# SCH_Elektrisch_Schema_B_2022-10-22.net
KiCad netlist of a schematic drawn in EasyEDA
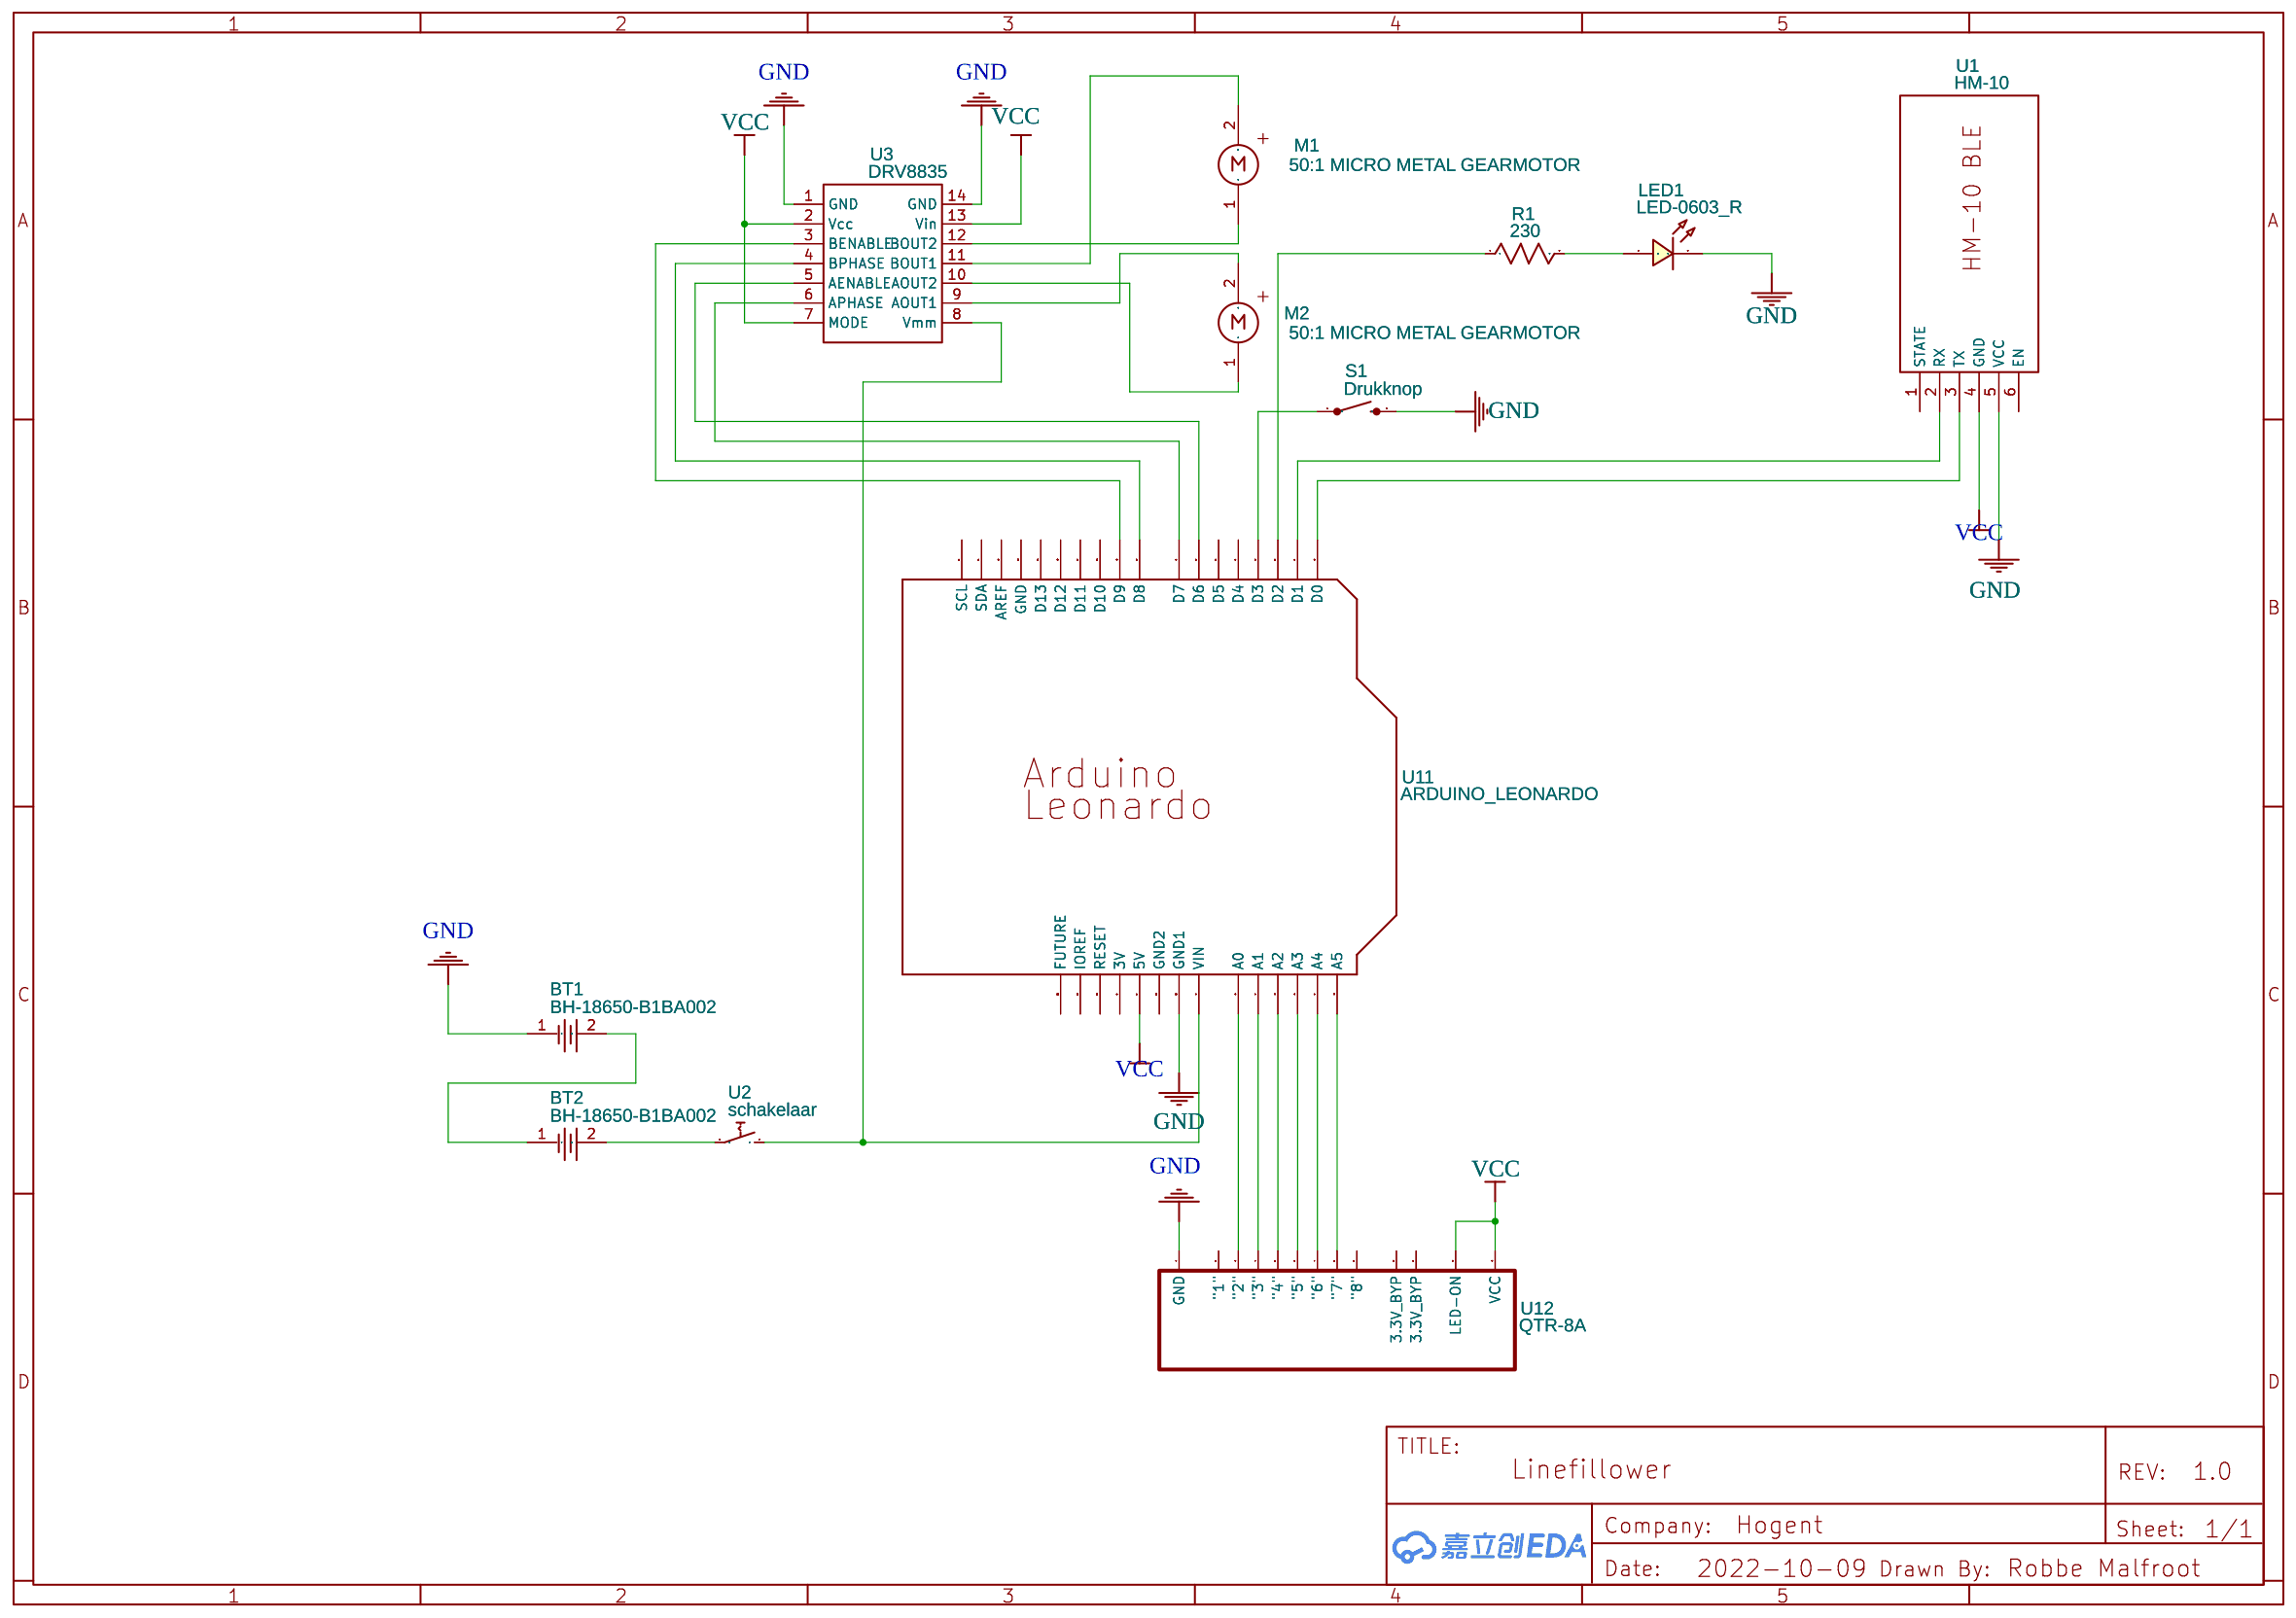
[diagram p0: Elektrisch schema B]
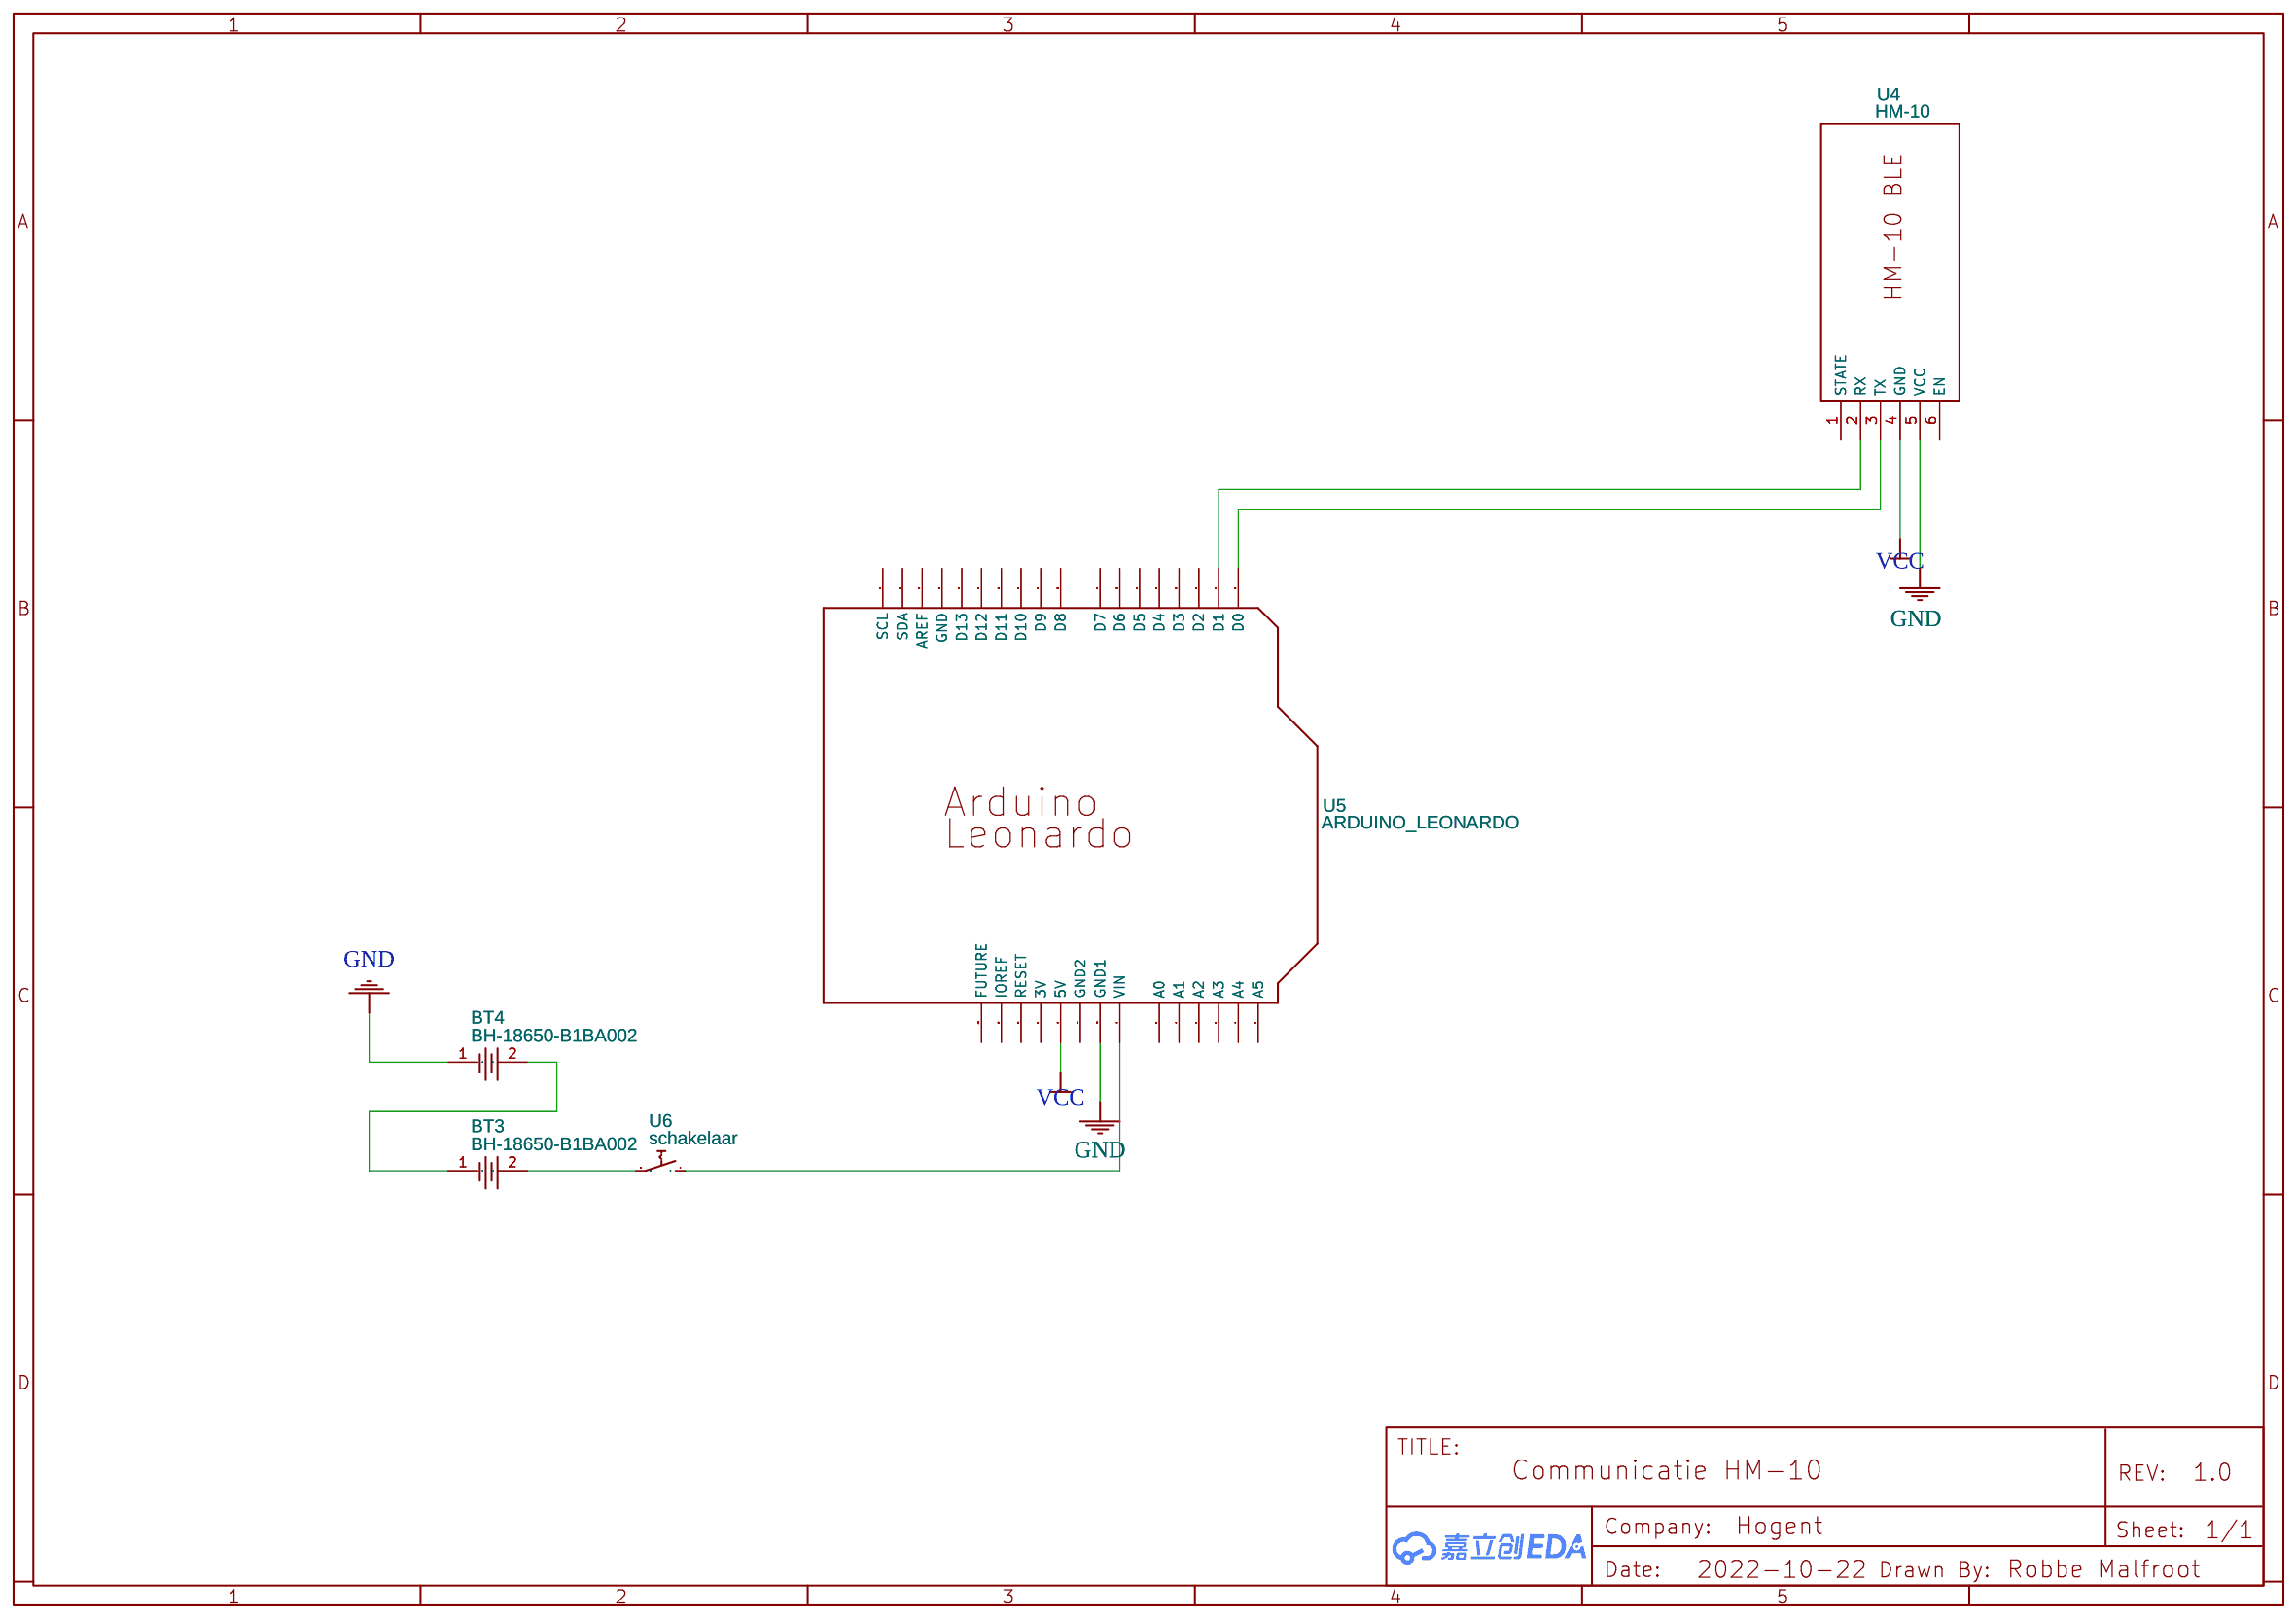
[diagram p1: Communicatie_HM-10]
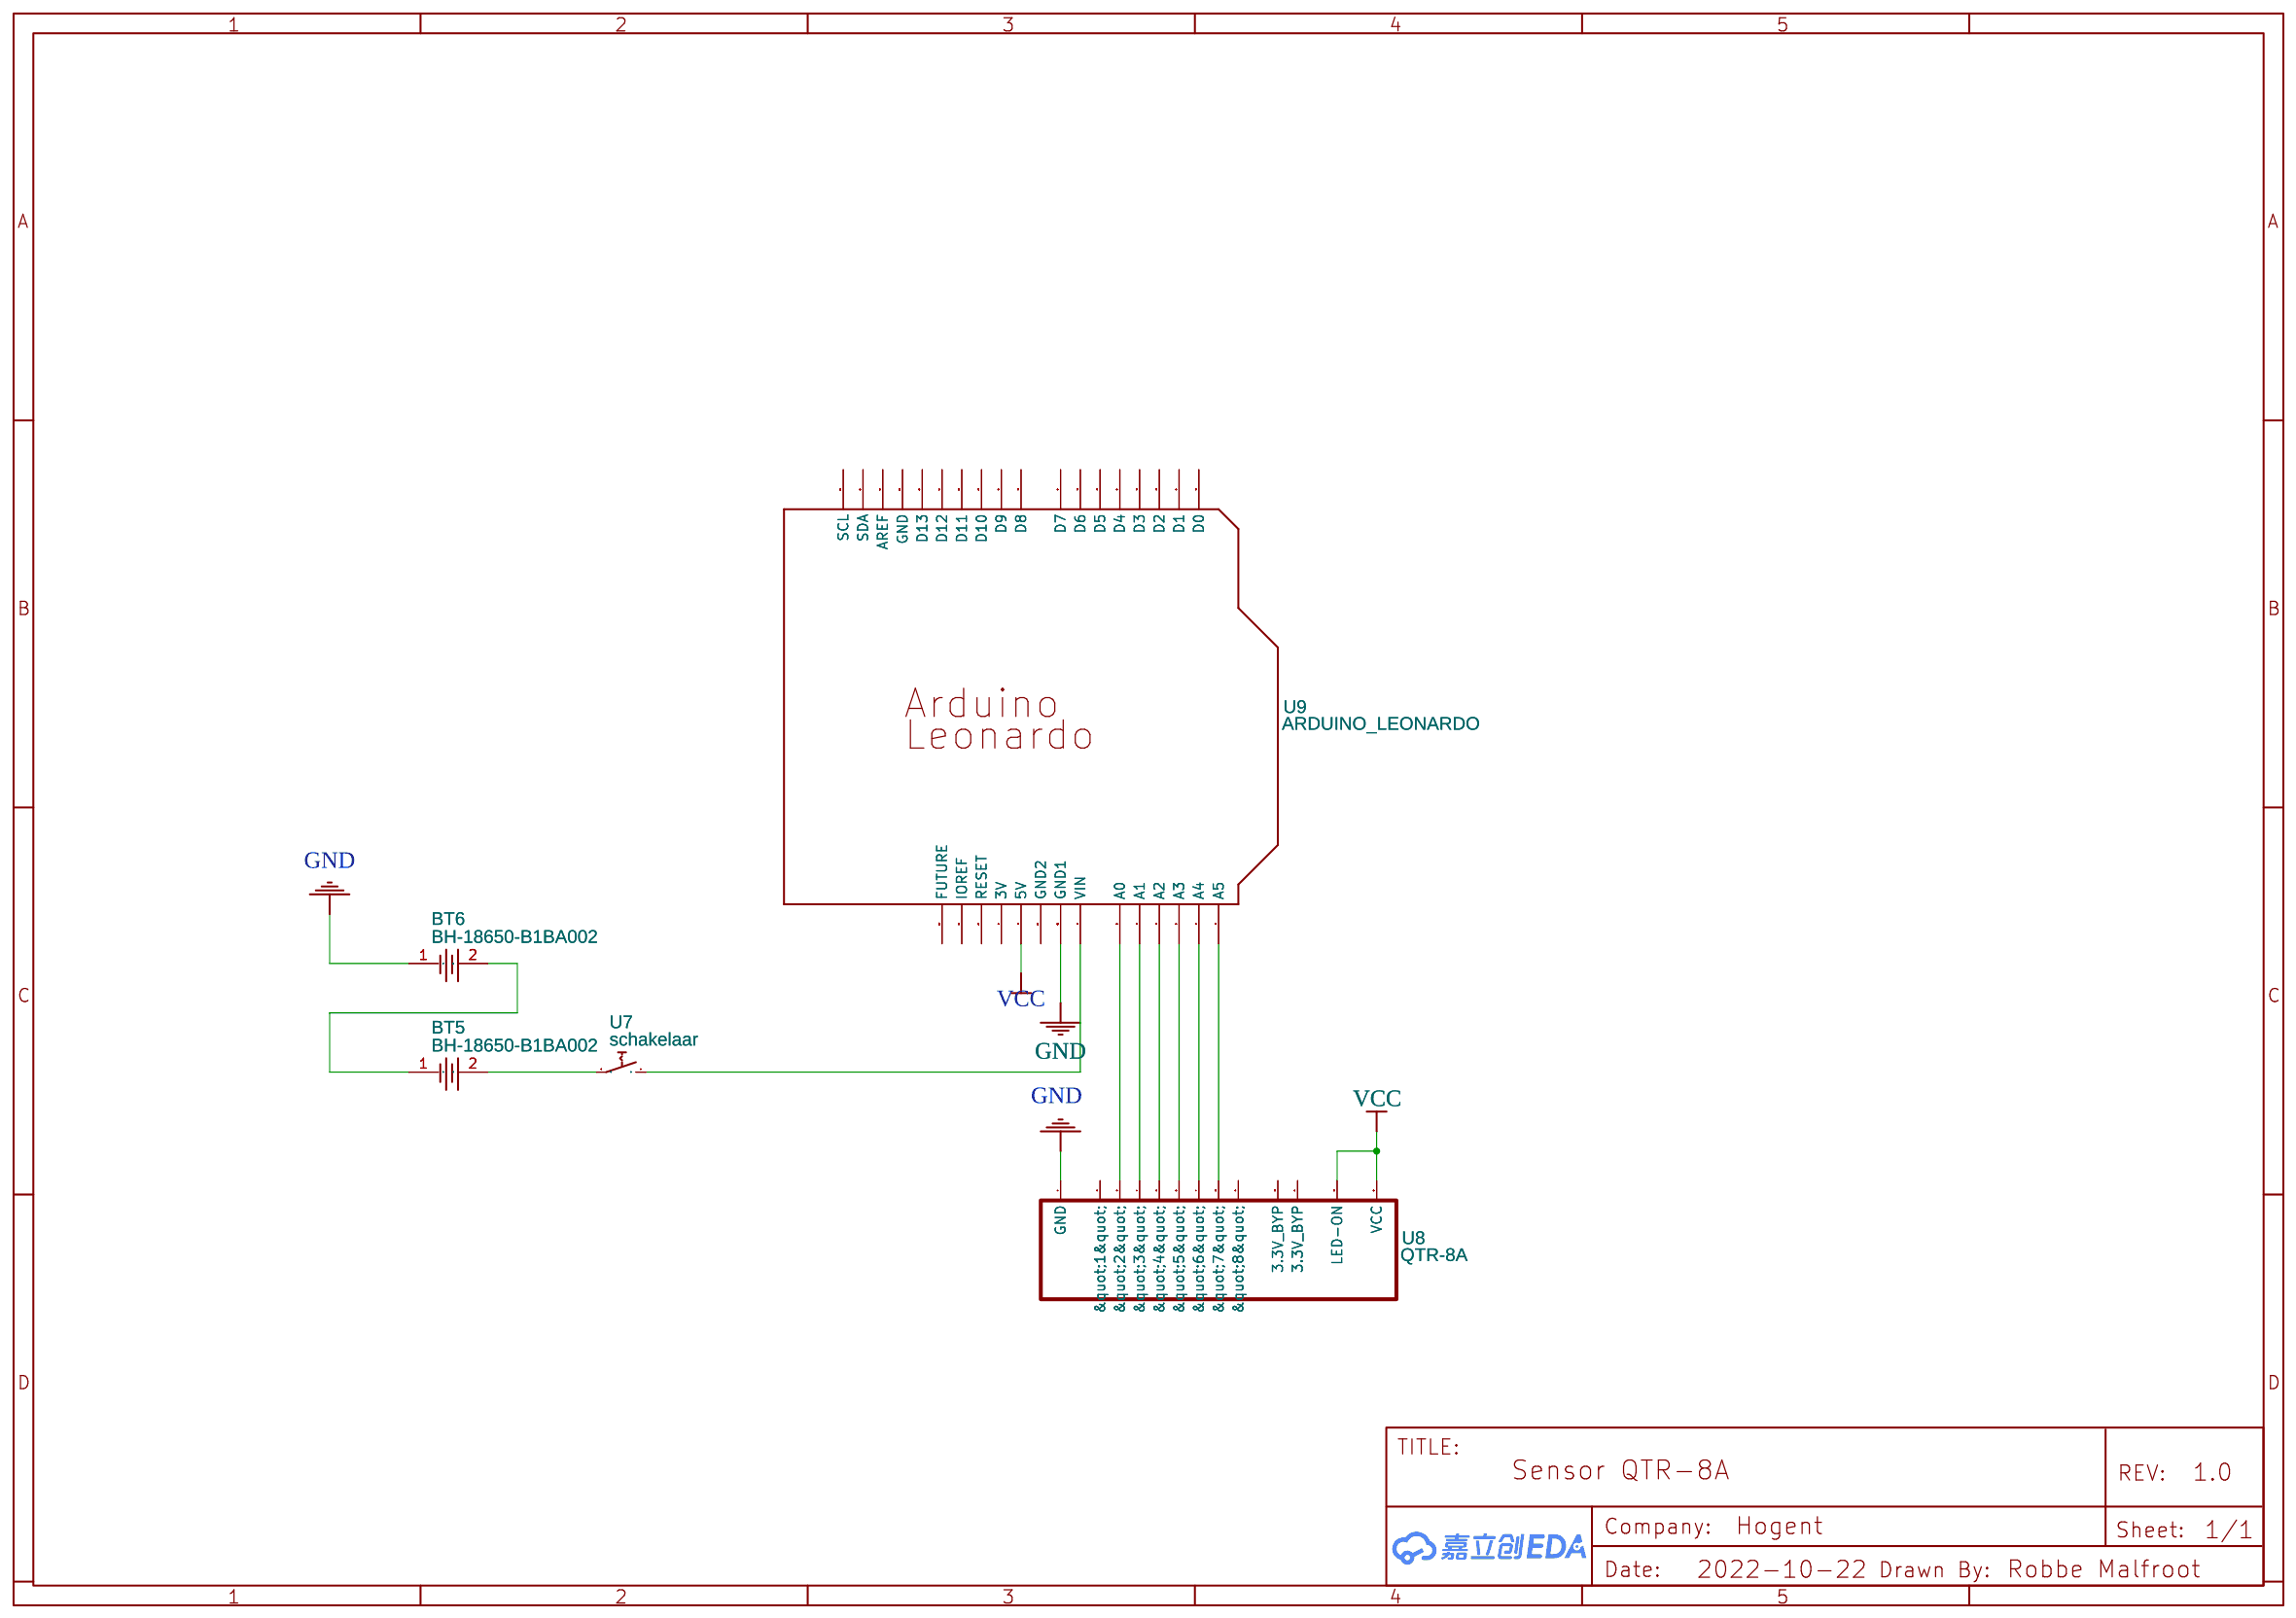
[diagram p2: QTR-8A]
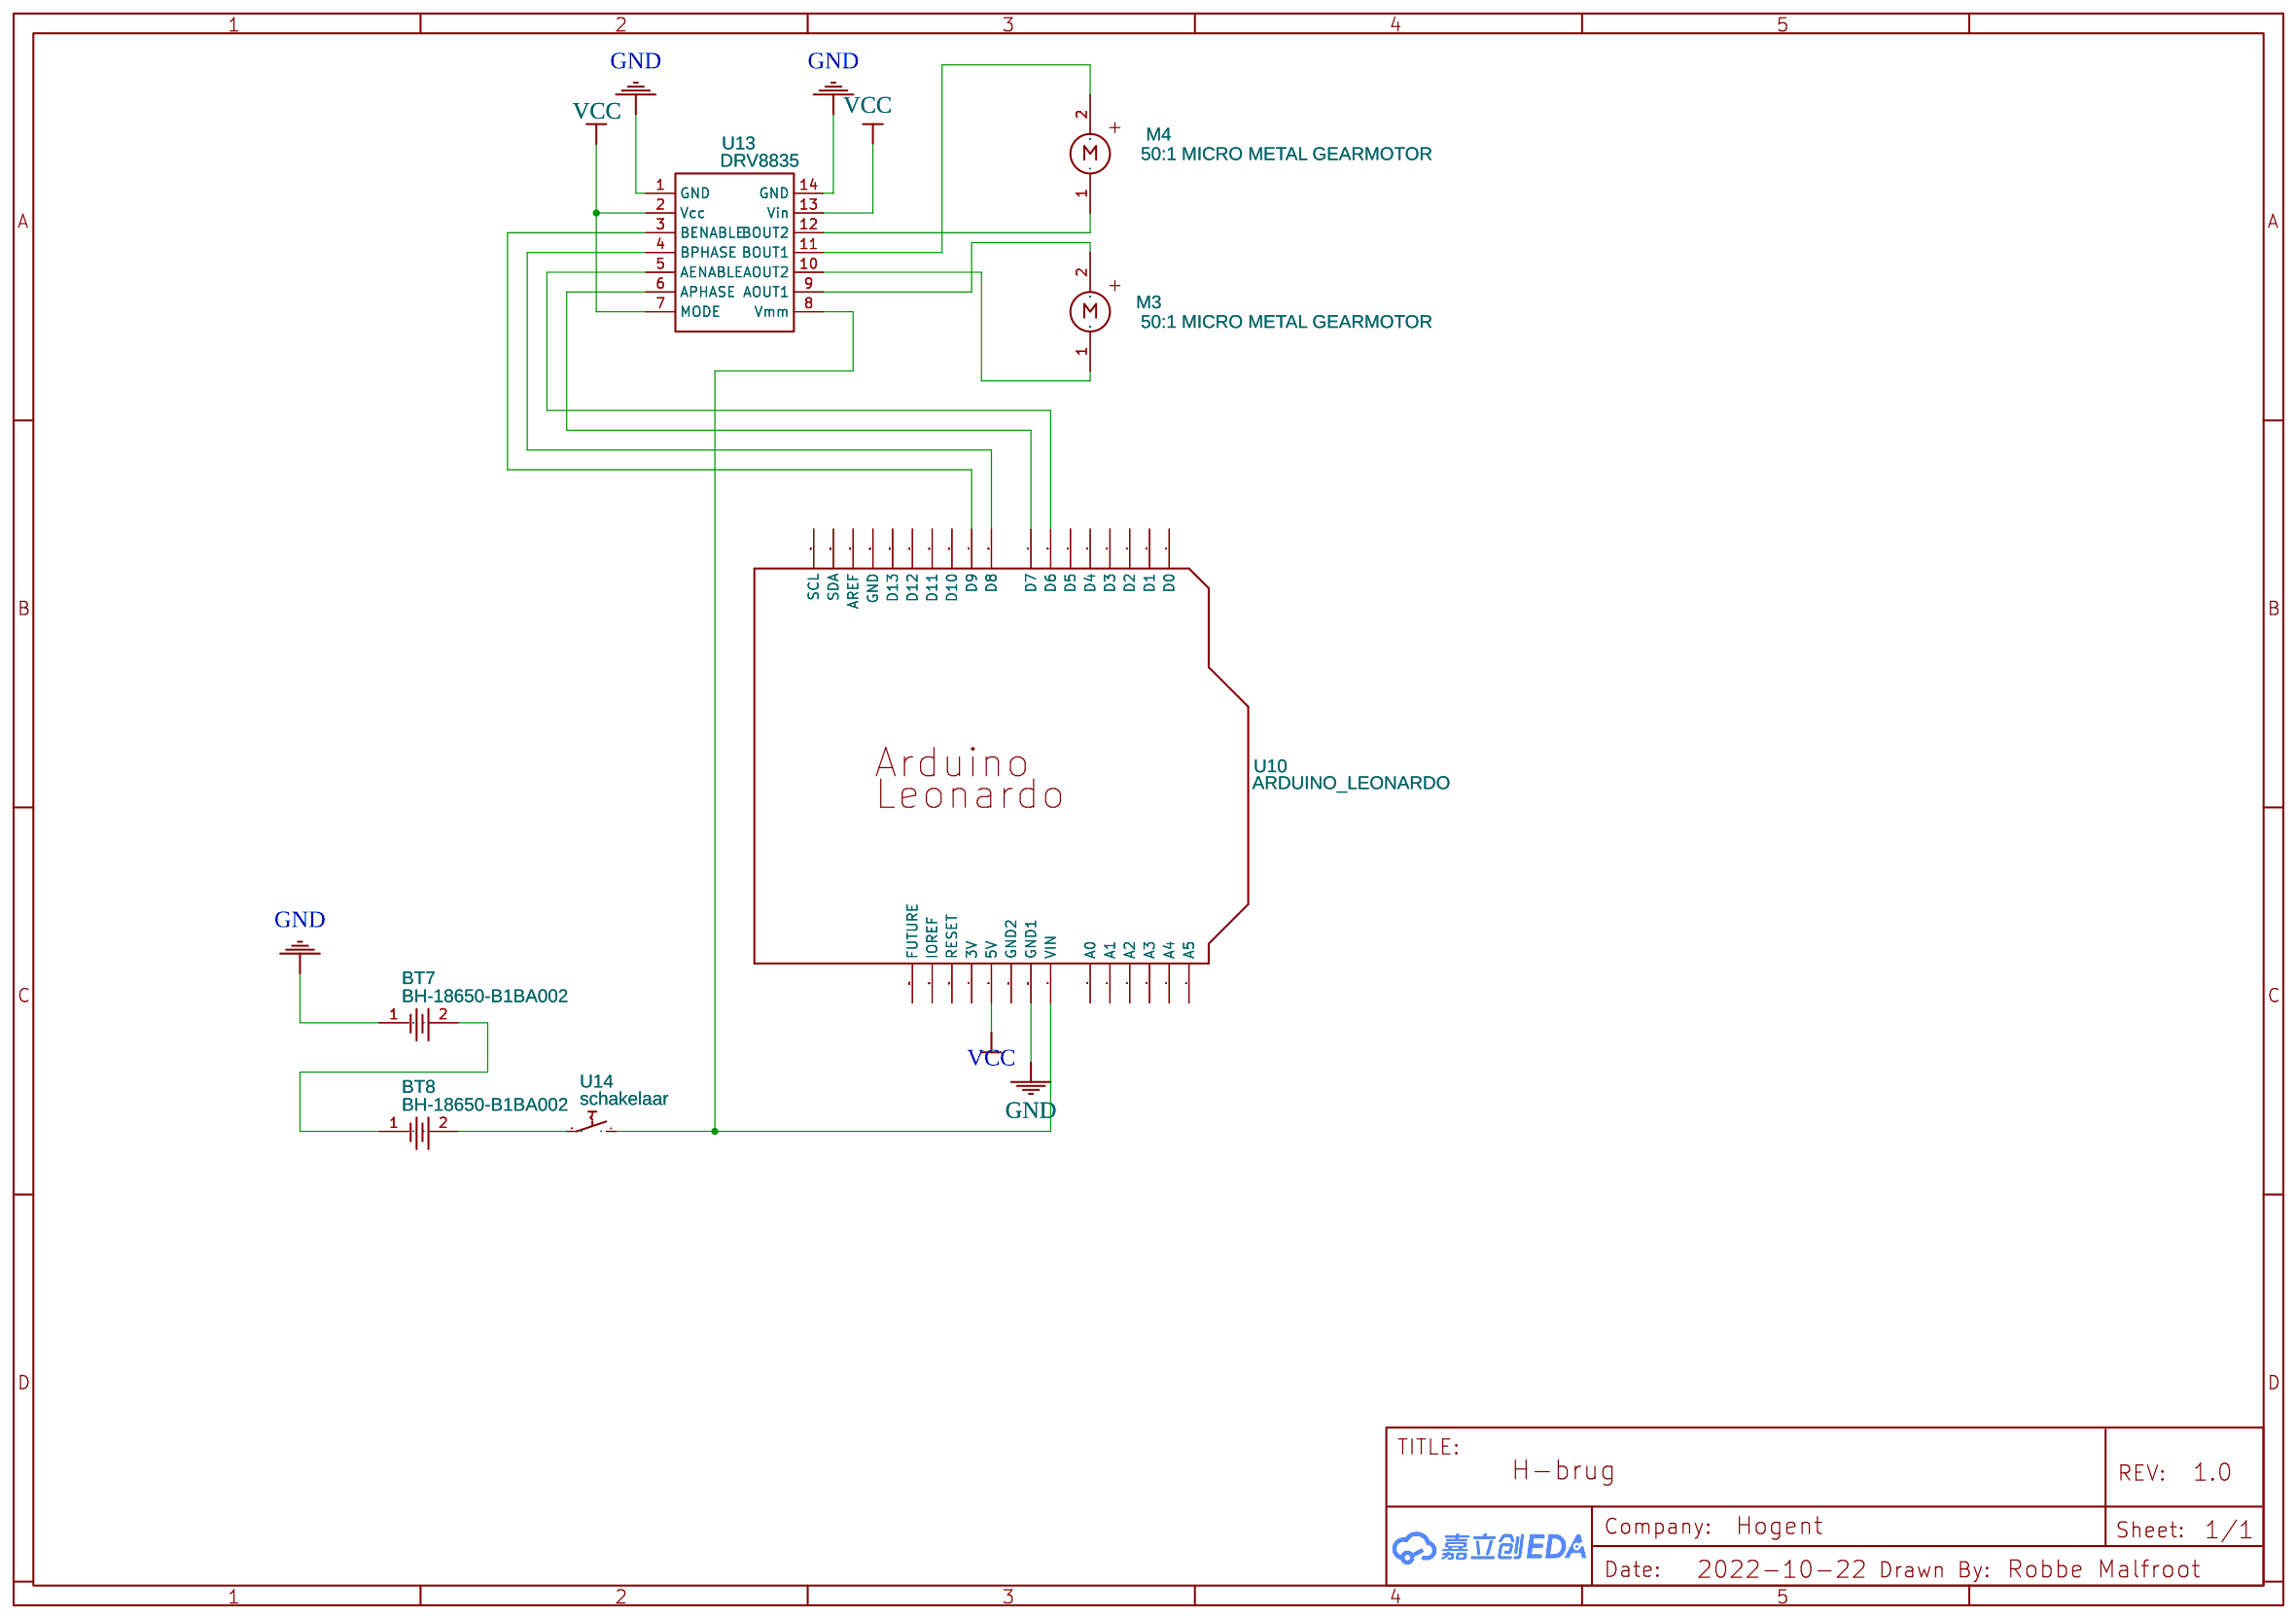
[diagram p3: H-brug DRV8835]

(export (version "E")
  (design (tool "Eeschema 10.0.6"))
  (components
    (comp (ref "BT1")
      (value "BH-18650-B1BA002")
      (fields (field (name "BOM_Supplier Part") "C2988620"))
      (libsource (lib "") (part "BH-18650-B1BA002"))
    )
    (comp (ref "BT2")
      (value "BH-18650-B1BA002")
      (fields (field (name "BOM_Supplier Part") "C2988620"))
      (libsource (lib "") (part "BH-18650-B1BA002"))
    )
    (comp (ref "LED1")
      (value "LED-0603_R")
      (fields
        (field (name "BOM_Manufacturer Part") "19-217/R6C-AL1M2VY/3T")
        (field (name "BOM_Supplier Part") "C72044")
      )
      (libsource (lib "") (part "LED-0603_R"))
    )
    (comp (ref "M1")
      (value "50:1 MICRO METAL GEARMOTOR")
      (fields
        (field (name "BOM_Manufacturer Part") "10:1 Micro Metal Gearmotor HPCB 6V with Extended Motor Shaft")
        (field (name "BOM_Supplier Part") "3071")
      )
      (libsource (lib "") (part "10{colon}1 MICRO METAL GEARMOTOR eskere"))
    )
    (comp (ref "M2")
      (value "50:1 MICRO METAL GEARMOTOR")
      (fields
        (field (name "BOM_Manufacturer Part") "10:1 Micro Metal Gearmotor HPCB 6V with Extended Motor Shaft")
        (field (name "BOM_Supplier Part") "3071")
      )
      (libsource (lib "") (part "10{colon}1 MICRO METAL GEARMOTOR eskere"))
    )
    (comp (ref "R1") (value "230") (libsource (lib "") (part "R_0603_US")))
    (comp (ref "S1") (value "Drukknop") (libsource (lib "") (part "Drukknop")))
    (comp (ref "U1") (value "HM-10") (libsource (lib "") (part "HM-10")))
    (comp (ref "U2") (value "schakelaar") (libsource (lib "") (part "schakelaar")))
    (comp (ref "U3") (value "DRV8835") (libsource (lib "") (part "DRV8835")))
    (comp (ref "U11") (value "ARDUINO_LEONARDO") (libsource (lib "") (part "ARDUINO_LEONARDO")))
    (comp (ref "U12")
      (value "QTR-8A")
      (fields (field (name "BOM_Supplier Part") "960"))
      (libsource (lib "") (part "QTR-8A"))
    )
    (comp (ref "BT3")
      (value "BH-18650-B1BA002")
      (fields (field (name "BOM_Supplier Part") "C2988620"))
      (libsource (lib "") (part "BH-18650-B1BA002"))
    )
    (comp (ref "BT4")
      (value "BH-18650-B1BA002")
      (fields (field (name "BOM_Supplier Part") "C2988620"))
      (libsource (lib "") (part "BH-18650-B1BA002"))
    )
    (comp (ref "U4") (value "HM-10") (libsource (lib "") (part "HM-10")))
    (comp (ref "U5") (value "ARDUINO_LEONARDO") (libsource (lib "") (part "ARDUINO_LEONARDO")))
    (comp (ref "U6") (value "schakelaar") (libsource (lib "") (part "schakelaar")))
    (comp (ref "BT5")
      (value "BH-18650-B1BA002")
      (fields (field (name "BOM_Supplier Part") "C2988620"))
      (libsource (lib "") (part "BH-18650-B1BA002"))
    )
    (comp (ref "BT6")
      (value "BH-18650-B1BA002")
      (fields (field (name "BOM_Supplier Part") "C2988620"))
      (libsource (lib "") (part "BH-18650-B1BA002"))
    )
    (comp (ref "U7") (value "schakelaar") (libsource (lib "") (part "schakelaar")))
    (comp (ref "U8")
      (value "QTR-8A")
      (fields (field (name "BOM_Supplier Part") "960"))
      (libsource (lib "") (part "QTR-8A"))
    )
    (comp (ref "U9") (value "ARDUINO_LEONARDO") (libsource (lib "") (part "ARDUINO_LEONARDO")))
    (comp (ref "BT7")
      (value "BH-18650-B1BA002")
      (fields (field (name "BOM_Supplier Part") "C2988620"))
      (libsource (lib "") (part "BH-18650-B1BA002"))
    )
    (comp (ref "BT8")
      (value "BH-18650-B1BA002")
      (fields (field (name "BOM_Supplier Part") "C2988620"))
      (libsource (lib "") (part "BH-18650-B1BA002"))
    )
    (comp (ref "M3")
      (value "50:1 MICRO METAL GEARMOTOR")
      (fields
        (field (name "BOM_Manufacturer Part") "10:1 Micro Metal Gearmotor HPCB 6V with Extended Motor Shaft")
        (field (name "BOM_Supplier Part") "3071")
      )
      (libsource (lib "") (part "10{colon}1 MICRO METAL GEARMOTOR eskere"))
    )
    (comp (ref "M4")
      (value "50:1 MICRO METAL GEARMOTOR")
      (fields
        (field (name "BOM_Manufacturer Part") "10:1 Micro Metal Gearmotor HPCB 6V with Extended Motor Shaft")
        (field (name "BOM_Supplier Part") "3071")
      )
      (libsource (lib "") (part "10{colon}1 MICRO METAL GEARMOTOR eskere"))
    )
    (comp (ref "U10") (value "ARDUINO_LEONARDO") (libsource (lib "") (part "ARDUINO_LEONARDO")))
    (comp (ref "U13") (value "DRV8835") (libsource (lib "") (part "DRV8835")))
    (comp (ref "U14") (value "schakelaar") (libsource (lib "") (part "schakelaar")))
  )
  (nets
    (net (code "1") (name "GND") (class "Default")
      (node (ref "BT1") (pin "1") (pinfunction "1_1") (pintype "input"))
      (node (ref "BT4") (pin "1") (pinfunction "1_1") (pintype "input"))
      (node (ref "BT6") (pin "1") (pinfunction "1_1") (pintype "input"))
      (node (ref "BT7") (pin "1") (pinfunction "1_1") (pintype "input"))
      (node (ref "LED1") (pin "2") (pinfunction "2_2") (pintype "unspecified"))
      (node (ref "S1") (pin "2") (pinfunction "2_2") (pintype "unspecified"))
      (node (ref "U1") (pin "5") (pinfunction "VCC_5") (pintype "unspecified"))
      (node (ref "U10") (pin "GND$3") (pinfunction "GND1_GND$3") (pintype "passive"))
      (node (ref "U11") (pin "GND$3") (pinfunction "GND1_GND$3") (pintype "passive"))
      (node (ref "U12") (pin "1") (pinfunction "GND_1") (pintype "unspecified"))
      (node (ref "U13") (pin "1") (pinfunction "GND_1") (pintype "unspecified"))
      (node (ref "U13") (pin "14") (pinfunction "GND_14") (pintype "unspecified"))
      (node (ref "U3") (pin "1") (pinfunction "GND_1") (pintype "unspecified"))
      (node (ref "U3") (pin "14") (pinfunction "GND_14") (pintype "unspecified"))
      (node (ref "U4") (pin "5") (pinfunction "VCC_5") (pintype "unspecified"))
      (node (ref "U5") (pin "GND$3") (pinfunction "GND1_GND$3") (pintype "passive"))
      (node (ref "U8") (pin "1") (pinfunction "GND_1") (pintype "unspecified"))
      (node (ref "U9") (pin "GND$3") (pinfunction "GND1_GND$3") (pintype "passive"))
    )
    (net (code "2") (name "Net-(BT1-Pad2)") (class "Default")
      (node (ref "BT1") (pin "2") (pinfunction "2_2") (pintype "input"))
      (node (ref "BT2") (pin "1") (pinfunction "1_1") (pintype "input"))
    )
    (net (code "3") (name "Net-(BT2-Pad2)") (class "Default")
      (node (ref "BT2") (pin "2") (pinfunction "2_2") (pintype "input"))
      (node (ref "U2") (pin "2") (pinfunction "2_2") (pintype "unspecified"))
    )
    (net (code "4") (name "Net-(BT3-Pad1)") (class "Default")
      (node (ref "BT3") (pin "1") (pinfunction "1_1") (pintype "input"))
      (node (ref "BT4") (pin "2") (pinfunction "2_2") (pintype "input"))
    )
    (net (code "5") (name "Net-(BT3-Pad2)") (class "Default")
      (node (ref "BT3") (pin "2") (pinfunction "2_2") (pintype "input"))
      (node (ref "U6") (pin "2") (pinfunction "2_2") (pintype "unspecified"))
    )
    (net (code "6") (name "Net-(BT5-Pad1)") (class "Default")
      (node (ref "BT5") (pin "1") (pinfunction "1_1") (pintype "input"))
      (node (ref "BT6") (pin "2") (pinfunction "2_2") (pintype "input"))
    )
    (net (code "7") (name "Net-(BT5-Pad2)") (class "Default")
      (node (ref "BT5") (pin "2") (pinfunction "2_2") (pintype "input"))
      (node (ref "U7") (pin "2") (pinfunction "2_2") (pintype "unspecified"))
    )
    (net (code "8") (name "Net-(BT7-Pad2)") (class "Default")
      (node (ref "BT7") (pin "2") (pinfunction "2_2") (pintype "input"))
      (node (ref "BT8") (pin "1") (pinfunction "1_1") (pintype "input"))
    )
    (net (code "9") (name "Net-(BT8-Pad2)") (class "Default")
      (node (ref "BT8") (pin "2") (pinfunction "2_2") (pintype "input"))
      (node (ref "U14") (pin "2") (pinfunction "2_2") (pintype "unspecified"))
    )
    (net (code "10") (name "Net-(LED1-Pad1)") (class "Default")
      (node (ref "LED1") (pin "1") (pinfunction "1_1") (pintype "unspecified"))
      (node (ref "R1") (pin "2") (pinfunction "2_2") (pintype "unspecified"))
    )
    (net (code "11") (name "Net-(R1-Pad1)") (class "Default")
      (node (ref "R1") (pin "1") (pinfunction "1_1") (pintype "unspecified"))
      (node (ref "U11") (pin "D2") (pinfunction "D2_D2") (pintype "unspecified"))
    )
    (net (code "12") (name "Net-(S1-Pad1)") (class "Default")
      (node (ref "S1") (pin "1") (pinfunction "1_1") (pintype "unspecified"))
      (node (ref "U11") (pin "D3") (pinfunction "D3_D3") (pintype "unspecified"))
    )
    (net (code "13") (name "Net-(U1-RX)") (class "Default")
      (node (ref "U1") (pin "2") (pinfunction "RX_2") (pintype "unspecified"))
      (node (ref "U11") (pin "D1") (pinfunction "D1_D1") (pintype "unspecified"))
    )
    (net (code "14") (name "Net-(U1-TX)") (class "Default")
      (node (ref "U1") (pin "3") (pinfunction "TX_3") (pintype "unspecified"))
      (node (ref "U11") (pin "D0") (pinfunction "D0_D0") (pintype "unspecified"))
    )
    (net (code "15") (name "Net-(U3-AENABLE)") (class "Default")
      (node (ref "U11") (pin "D6") (pinfunction "D6_D6") (pintype "unspecified"))
      (node (ref "U3") (pin "5") (pinfunction "AENABLE_5") (pintype "unspecified"))
    )
    (net (code "16") (name "Net-(U3-AOUT1)") (class "Default")
      (node (ref "M2") (pin "2") (pinfunction "2_2") (pintype "unspecified"))
      (node (ref "U3") (pin "9") (pinfunction "AOUT1_9") (pintype "unspecified"))
    )
    (net (code "17") (name "Net-(U3-AOUT2)") (class "Default")
      (node (ref "M2") (pin "1") (pinfunction "1_1") (pintype "unspecified"))
      (node (ref "U3") (pin "10") (pinfunction "AOUT2_10") (pintype "unspecified"))
    )
    (net (code "18") (name "Net-(U3-APHASE)") (class "Default")
      (node (ref "U11") (pin "D7") (pinfunction "D7_D7") (pintype "unspecified"))
      (node (ref "U3") (pin "6") (pinfunction "APHASE_6") (pintype "unspecified"))
    )
    (net (code "19") (name "Net-(U3-BENABLE)") (class "Default")
      (node (ref "U11") (pin "D9") (pinfunction "D9_D9") (pintype "unspecified"))
      (node (ref "U3") (pin "3") (pinfunction "BENABLE_3") (pintype "unspecified"))
    )
    (net (code "20") (name "Net-(U3-BOUT1)") (class "Default")
      (node (ref "M1") (pin "2") (pinfunction "2_2") (pintype "unspecified"))
      (node (ref "U3") (pin "11") (pinfunction "BOUT1_11") (pintype "unspecified"))
    )
    (net (code "21") (name "Net-(U3-BOUT2)") (class "Default")
      (node (ref "M1") (pin "1") (pinfunction "1_1") (pintype "unspecified"))
      (node (ref "U3") (pin "12") (pinfunction "BOUT2_12") (pintype "unspecified"))
    )
    (net (code "22") (name "Net-(U3-BPHASE)") (class "Default")
      (node (ref "U11") (pin "D8") (pinfunction "D8_D8") (pintype "unspecified"))
      (node (ref "U3") (pin "4") (pinfunction "BPHASE_4") (pintype "unspecified"))
    )
    (net (code "23") (name "Net-(U3-Vmm)") (class "Default")
      (node (ref "U11") (pin "VIN") (pinfunction "VIN_VIN") (pintype "passive"))
      (node (ref "U2") (pin "1") (pinfunction "1_1") (pintype "unspecified"))
      (node (ref "U3") (pin "8") (pinfunction "Vmm_8") (pintype "unspecified"))
    )
    (net (code "24") (name "Net-(U4-RX)") (class "Default")
      (node (ref "U4") (pin "2") (pinfunction "RX_2") (pintype "unspecified"))
      (node (ref "U5") (pin "D1") (pinfunction "D1_D1") (pintype "unspecified"))
    )
    (net (code "25") (name "Net-(U4-TX)") (class "Default")
      (node (ref "U4") (pin "3") (pinfunction "TX_3") (pintype "unspecified"))
      (node (ref "U5") (pin "D0") (pinfunction "D0_D0") (pintype "unspecified"))
    )
    (net (code "26") (name "Net-(U5-PadVIN)") (class "Default")
      (node (ref "U5") (pin "VIN") (pinfunction "VIN_VIN") (pintype "passive"))
      (node (ref "U6") (pin "1") (pinfunction "1_1") (pintype "unspecified"))
    )
    (net (code "27") (name "Net-(U7-Pad1)") (class "Default")
      (node (ref "U7") (pin "1") (pinfunction "1_1") (pintype "unspecified"))
      (node (ref "U9") (pin "VIN") (pinfunction "VIN_VIN") (pintype "passive"))
    )
    (net (code "28") (name "Net-(U8-&quot;2&quot;)") (class "Default")
      (node (ref "U8") (pin "3") (pinfunction "&quot;2&quot;_3") (pintype "unspecified"))
      (node (ref "U9") (pin "A0") (pinfunction "A0_A0") (pintype "unspecified"))
    )
    (net (code "29") (name "Net-(U8-&quot;3&quot;)") (class "Default")
      (node (ref "U8") (pin "4") (pinfunction "&quot;3&quot;_4") (pintype "unspecified"))
      (node (ref "U9") (pin "A1") (pinfunction "A1_A1") (pintype "unspecified"))
    )
    (net (code "30") (name "Net-(U8-&quot;4&quot;)") (class "Default")
      (node (ref "U8") (pin "5") (pinfunction "&quot;4&quot;_5") (pintype "unspecified"))
      (node (ref "U9") (pin "A2") (pinfunction "A2_A2") (pintype "unspecified"))
    )
    (net (code "31") (name "Net-(U8-&quot;5&quot;)") (class "Default")
      (node (ref "U8") (pin "6") (pinfunction "&quot;5&quot;_6") (pintype "unspecified"))
      (node (ref "U9") (pin "A3") (pinfunction "A3_A3") (pintype "unspecified"))
    )
    (net (code "32") (name "Net-(U8-&quot;6&quot;)") (class "Default")
      (node (ref "U8") (pin "7") (pinfunction "&quot;6&quot;_7") (pintype "unspecified"))
      (node (ref "U9") (pin "A4") (pinfunction "A4_A4") (pintype "unspecified"))
    )
    (net (code "33") (name "Net-(U8-&quot;7&quot;)") (class "Default")
      (node (ref "U8") (pin "8") (pinfunction "&quot;7&quot;_8") (pintype "unspecified"))
      (node (ref "U9") (pin "A5") (pinfunction "A5_A5") (pintype "unspecified"))
    )
    (net (code "34") (name "Net-(U12-\"2\")") (class "Default")
      (node (ref "U11") (pin "A0") (pinfunction "A0_A0") (pintype "unspecified"))
      (node (ref "U12") (pin "3") (pinfunction "\"2\"_3") (pintype "unspecified"))
    )
    (net (code "35") (name "Net-(U12-\"3\")") (class "Default")
      (node (ref "U11") (pin "A1") (pinfunction "A1_A1") (pintype "unspecified"))
      (node (ref "U12") (pin "4") (pinfunction "\"3\"_4") (pintype "unspecified"))
    )
    (net (code "36") (name "Net-(U12-\"4\")") (class "Default")
      (node (ref "U11") (pin "A2") (pinfunction "A2_A2") (pintype "unspecified"))
      (node (ref "U12") (pin "5") (pinfunction "\"4\"_5") (pintype "unspecified"))
    )
    (net (code "37") (name "Net-(U12-\"5\")") (class "Default")
      (node (ref "U11") (pin "A3") (pinfunction "A3_A3") (pintype "unspecified"))
      (node (ref "U12") (pin "6") (pinfunction "\"5\"_6") (pintype "unspecified"))
    )
    (net (code "38") (name "Net-(U12-\"6\")") (class "Default")
      (node (ref "U11") (pin "A4") (pinfunction "A4_A4") (pintype "unspecified"))
      (node (ref "U12") (pin "7") (pinfunction "\"6\"_7") (pintype "unspecified"))
    )
    (net (code "39") (name "Net-(U12-\"7\")") (class "Default")
      (node (ref "U11") (pin "A5") (pinfunction "A5_A5") (pintype "unspecified"))
      (node (ref "U12") (pin "8") (pinfunction "\"7\"_8") (pintype "unspecified"))
    )
    (net (code "40") (name "Net-(U13-AENABLE)") (class "Default")
      (node (ref "U10") (pin "D6") (pinfunction "D6_D6") (pintype "unspecified"))
      (node (ref "U13") (pin "5") (pinfunction "AENABLE_5") (pintype "unspecified"))
    )
    (net (code "41") (name "Net-(U13-AOUT1)") (class "Default")
      (node (ref "M3") (pin "2") (pinfunction "2_2") (pintype "unspecified"))
      (node (ref "U13") (pin "9") (pinfunction "AOUT1_9") (pintype "unspecified"))
    )
    (net (code "42") (name "Net-(U13-AOUT2)") (class "Default")
      (node (ref "M3") (pin "1") (pinfunction "1_1") (pintype "unspecified"))
      (node (ref "U13") (pin "10") (pinfunction "AOUT2_10") (pintype "unspecified"))
    )
    (net (code "43") (name "Net-(U13-APHASE)") (class "Default")
      (node (ref "U10") (pin "D7") (pinfunction "D7_D7") (pintype "unspecified"))
      (node (ref "U13") (pin "6") (pinfunction "APHASE_6") (pintype "unspecified"))
    )
    (net (code "44") (name "Net-(U13-BENABLE)") (class "Default")
      (node (ref "U10") (pin "D9") (pinfunction "D9_D9") (pintype "unspecified"))
      (node (ref "U13") (pin "3") (pinfunction "BENABLE_3") (pintype "unspecified"))
    )
    (net (code "45") (name "Net-(U13-BOUT1)") (class "Default")
      (node (ref "M4") (pin "2") (pinfunction "2_2") (pintype "unspecified"))
      (node (ref "U13") (pin "11") (pinfunction "BOUT1_11") (pintype "unspecified"))
    )
    (net (code "46") (name "Net-(U13-BOUT2)") (class "Default")
      (node (ref "M4") (pin "1") (pinfunction "1_1") (pintype "unspecified"))
      (node (ref "U13") (pin "12") (pinfunction "BOUT2_12") (pintype "unspecified"))
    )
    (net (code "47") (name "Net-(U13-BPHASE)") (class "Default")
      (node (ref "U10") (pin "D8") (pinfunction "D8_D8") (pintype "unspecified"))
      (node (ref "U13") (pin "4") (pinfunction "BPHASE_4") (pintype "unspecified"))
    )
    (net (code "48") (name "Net-(U13-Vmm)") (class "Default")
      (node (ref "U10") (pin "VIN") (pinfunction "VIN_VIN") (pintype "passive"))
      (node (ref "U13") (pin "8") (pinfunction "Vmm_8") (pintype "unspecified"))
      (node (ref "U14") (pin "1") (pinfunction "1_1") (pintype "unspecified"))
    )
    (net (code "49") (name "VCC") (class "Default")
      (node (ref "U1") (pin "4") (pinfunction "GND_4") (pintype "unspecified"))
      (node (ref "U10") (pin "5V") (pinfunction "5V_5V") (pintype "passive"))
      (node (ref "U11") (pin "5V") (pinfunction "5V_5V") (pintype "passive"))
      (node (ref "U12") (pin "12") (pinfunction "VCC_12") (pintype "unspecified"))
      (node (ref "U13") (pin "13") (pinfunction "Vin_13") (pintype "unspecified"))
      (node (ref "U13") (pin "2") (pinfunction "Vcc_2") (pintype "unspecified"))
      (node (ref "U13") (pin "7") (pinfunction "MODE_7") (pintype "unspecified"))
      (node (ref "U3") (pin "13") (pinfunction "Vin_13") (pintype "unspecified"))
      (node (ref "U3") (pin "2") (pinfunction "Vcc_2") (pintype "unspecified"))
      (node (ref "U3") (pin "7") (pinfunction "MODE_7") (pintype "unspecified"))
      (node (ref "U4") (pin "4") (pinfunction "GND_4") (pintype "unspecified"))
      (node (ref "U5") (pin "5V") (pinfunction "5V_5V") (pintype "passive"))
      (node (ref "U8") (pin "12") (pinfunction "LED-ON_12") (pintype "unspecified"))
      (node (ref "U9") (pin "5V") (pinfunction "5V_5V") (pintype "passive"))
    )
    (net (code "50") (name "unconnected-(U1-EN-Pad6)") (class "Default")
      (node (ref "U1") (pin "6") (pinfunction "EN_6") (pintype "unspecified"))
    )
    (net (code "51") (name "unconnected-(U1-STATE-Pad1)") (class "Default")
      (node (ref "U1") (pin "1") (pinfunction "STATE_1") (pintype "unspecified"))
    )
    (net (code "52") (name "unconnected-(U4-EN-Pad6)") (class "Default")
      (node (ref "U4") (pin "6") (pinfunction "EN_6") (pintype "unspecified"))
    )
    (net (code "53") (name "unconnected-(U4-STATE-Pad1)") (class "Default")
      (node (ref "U4") (pin "1") (pinfunction "STATE_1") (pintype "unspecified"))
    )
    (net (code "54") (name "unconnected-(U5-FUTURE-PadRESERVED)") (class "Default")
      (node (ref "U5") (pin "RESERVED") (pinfunction "FUTURE_RESERVED") (pintype "unspecified"))
    )
    (net (code "55") (name "unconnected-(U5-GND2-PadGND$2)") (class "Default")
      (node (ref "U5") (pin "GND$2") (pinfunction "GND2_GND$2") (pintype "passive"))
    )
    (net (code "56") (name "unconnected-(U5-Pad3V)") (class "Default")
      (node (ref "U5") (pin "3V") (pinfunction "3V_3V") (pintype "passive"))
    )
    (net (code "57") (name "unconnected-(U5-PadA0)") (class "Default")
      (node (ref "U5") (pin "A0") (pinfunction "A0_A0") (pintype "unspecified"))
    )
    (net (code "58") (name "unconnected-(U5-PadA1)") (class "Default")
      (node (ref "U5") (pin "A1") (pinfunction "A1_A1") (pintype "unspecified"))
    )
    (net (code "59") (name "unconnected-(U5-PadA2)") (class "Default")
      (node (ref "U5") (pin "A2") (pinfunction "A2_A2") (pintype "unspecified"))
    )
    (net (code "60") (name "unconnected-(U5-PadA3)") (class "Default")
      (node (ref "U5") (pin "A3") (pinfunction "A3_A3") (pintype "unspecified"))
    )
    (net (code "61") (name "unconnected-(U5-PadA4)") (class "Default")
      (node (ref "U5") (pin "A4") (pinfunction "A4_A4") (pintype "unspecified"))
    )
    (net (code "62") (name "unconnected-(U5-PadA5)") (class "Default")
      (node (ref "U5") (pin "A5") (pinfunction "A5_A5") (pintype "unspecified"))
    )
    (net (code "63") (name "unconnected-(U5-PadAREF)") (class "Default")
      (node (ref "U5") (pin "AREF") (pinfunction "AREF_AREF") (pintype "unspecified"))
    )
    (net (code "64") (name "unconnected-(U5-PadD2)") (class "Default")
      (node (ref "U5") (pin "D2") (pinfunction "D2_D2") (pintype "unspecified"))
    )
    (net (code "65") (name "unconnected-(U5-PadD3)") (class "Default")
      (node (ref "U5") (pin "D3") (pinfunction "D3_D3") (pintype "unspecified"))
    )
    (net (code "66") (name "unconnected-(U5-PadD4)") (class "Default")
      (node (ref "U5") (pin "D4") (pinfunction "D4_D4") (pintype "unspecified"))
    )
    (net (code "67") (name "unconnected-(U5-PadD5)") (class "Default")
      (node (ref "U5") (pin "D5") (pinfunction "D5_D5") (pintype "unspecified"))
    )
    (net (code "68") (name "unconnected-(U5-PadD6)") (class "Default")
      (node (ref "U5") (pin "D6") (pinfunction "D6_D6") (pintype "unspecified"))
    )
    (net (code "69") (name "unconnected-(U5-PadD7)") (class "Default")
      (node (ref "U5") (pin "D7") (pinfunction "D7_D7") (pintype "unspecified"))
    )
    (net (code "70") (name "unconnected-(U5-PadD8)") (class "Default")
      (node (ref "U5") (pin "D8") (pinfunction "D8_D8") (pintype "unspecified"))
    )
    (net (code "71") (name "unconnected-(U5-PadD9)") (class "Default")
      (node (ref "U5") (pin "D9") (pinfunction "D9_D9") (pintype "unspecified"))
    )
    (net (code "72") (name "unconnected-(U5-PadD10)") (class "Default")
      (node (ref "U5") (pin "D10") (pinfunction "D10_D10") (pintype "unspecified"))
    )
    (net (code "73") (name "unconnected-(U5-PadD11)") (class "Default")
      (node (ref "U5") (pin "D11") (pinfunction "D11_D11") (pintype "unspecified"))
    )
    (net (code "74") (name "unconnected-(U5-PadD12)") (class "Default")
      (node (ref "U5") (pin "D12") (pinfunction "D12_D12") (pintype "unspecified"))
    )
    (net (code "75") (name "unconnected-(U5-PadD13)") (class "Default")
      (node (ref "U5") (pin "D13") (pinfunction "D13_D13") (pintype "unspecified"))
    )
    (net (code "76") (name "unconnected-(U5-PadGND)") (class "Default")
      (node (ref "U5") (pin "GND") (pinfunction "GND_GND") (pintype "passive"))
    )
    (net (code "77") (name "unconnected-(U5-PadIOREF)") (class "Default")
      (node (ref "U5") (pin "IOREF") (pinfunction "IOREF_IOREF") (pintype "unspecified"))
    )
    (net (code "78") (name "unconnected-(U5-PadRESET)") (class "Default")
      (node (ref "U5") (pin "RESET") (pinfunction "RESET_RESET") (pintype "unspecified"))
    )
    (net (code "79") (name "unconnected-(U5-PadSCL)") (class "Default")
      (node (ref "U5") (pin "SCL") (pinfunction "SCL_SCL") (pintype "unspecified"))
    )
    (net (code "80") (name "unconnected-(U5-PadSDA)") (class "Default")
      (node (ref "U5") (pin "SDA") (pinfunction "SDA_SDA") (pintype "unspecified"))
    )
    (net (code "81") (name "unconnected-(U8-&quot;1&quot;-Pad2)") (class "Default")
      (node (ref "U8") (pin "2") (pinfunction "&quot;1&quot;_2") (pintype "unspecified"))
    )
    (net (code "82") (name "unconnected-(U8-&quot;8&quot;-Pad9)") (class "Default")
      (node (ref "U8") (pin "9") (pinfunction "&quot;8&quot;_9") (pintype "unspecified"))
    )
    (net (code "83") (name "unconnected-(U8-3.3V_BYP-Pad10)") (class "Default")
      (node (ref "U8") (pin "10") (pinfunction "3.3V_BYP_10") (pintype "unspecified"))
    )
    (net (code "84") (name "unconnected-(U8-3.3V_BYP-Pad11)") (class "Default")
      (node (ref "U8") (pin "11") (pinfunction "3.3V_BYP_11") (pintype "unspecified"))
    )
    (net (code "85") (name "unconnected-(U9-FUTURE-PadRESERVED)") (class "Default")
      (node (ref "U9") (pin "RESERVED") (pinfunction "FUTURE_RESERVED") (pintype "unspecified"))
    )
    (net (code "86") (name "unconnected-(U9-GND2-PadGND$2)") (class "Default")
      (node (ref "U9") (pin "GND$2") (pinfunction "GND2_GND$2") (pintype "passive"))
    )
    (net (code "87") (name "unconnected-(U9-Pad3V)") (class "Default")
      (node (ref "U9") (pin "3V") (pinfunction "3V_3V") (pintype "passive"))
    )
    (net (code "88") (name "unconnected-(U9-PadAREF)") (class "Default")
      (node (ref "U9") (pin "AREF") (pinfunction "AREF_AREF") (pintype "unspecified"))
    )
    (net (code "89") (name "unconnected-(U9-PadD0)") (class "Default")
      (node (ref "U9") (pin "D0") (pinfunction "D0_D0") (pintype "unspecified"))
    )
    (net (code "90") (name "unconnected-(U9-PadD1)") (class "Default")
      (node (ref "U9") (pin "D1") (pinfunction "D1_D1") (pintype "unspecified"))
    )
    (net (code "91") (name "unconnected-(U9-PadD2)") (class "Default")
      (node (ref "U9") (pin "D2") (pinfunction "D2_D2") (pintype "unspecified"))
    )
    (net (code "92") (name "unconnected-(U9-PadD3)") (class "Default")
      (node (ref "U9") (pin "D3") (pinfunction "D3_D3") (pintype "unspecified"))
    )
    (net (code "93") (name "unconnected-(U9-PadD4)") (class "Default")
      (node (ref "U9") (pin "D4") (pinfunction "D4_D4") (pintype "unspecified"))
    )
    (net (code "94") (name "unconnected-(U9-PadD5)") (class "Default")
      (node (ref "U9") (pin "D5") (pinfunction "D5_D5") (pintype "unspecified"))
    )
    (net (code "95") (name "unconnected-(U9-PadD6)") (class "Default")
      (node (ref "U9") (pin "D6") (pinfunction "D6_D6") (pintype "unspecified"))
    )
    (net (code "96") (name "unconnected-(U9-PadD7)") (class "Default")
      (node (ref "U9") (pin "D7") (pinfunction "D7_D7") (pintype "unspecified"))
    )
    (net (code "97") (name "unconnected-(U9-PadD8)") (class "Default")
      (node (ref "U9") (pin "D8") (pinfunction "D8_D8") (pintype "unspecified"))
    )
    (net (code "98") (name "unconnected-(U9-PadD9)") (class "Default")
      (node (ref "U9") (pin "D9") (pinfunction "D9_D9") (pintype "unspecified"))
    )
    (net (code "99") (name "unconnected-(U9-PadD10)") (class "Default")
      (node (ref "U9") (pin "D10") (pinfunction "D10_D10") (pintype "unspecified"))
    )
    (net (code "100") (name "unconnected-(U9-PadD11)") (class "Default")
      (node (ref "U9") (pin "D11") (pinfunction "D11_D11") (pintype "unspecified"))
    )
    (net (code "101") (name "unconnected-(U9-PadD12)") (class "Default")
      (node (ref "U9") (pin "D12") (pinfunction "D12_D12") (pintype "unspecified"))
    )
    (net (code "102") (name "unconnected-(U9-PadD13)") (class "Default")
      (node (ref "U9") (pin "D13") (pinfunction "D13_D13") (pintype "unspecified"))
    )
    (net (code "103") (name "unconnected-(U9-PadGND)") (class "Default")
      (node (ref "U9") (pin "GND") (pinfunction "GND_GND") (pintype "passive"))
    )
    (net (code "104") (name "unconnected-(U9-PadIOREF)") (class "Default")
      (node (ref "U9") (pin "IOREF") (pinfunction "IOREF_IOREF") (pintype "unspecified"))
    )
    (net (code "105") (name "unconnected-(U9-PadRESET)") (class "Default")
      (node (ref "U9") (pin "RESET") (pinfunction "RESET_RESET") (pintype "unspecified"))
    )
    (net (code "106") (name "unconnected-(U9-PadSCL)") (class "Default")
      (node (ref "U9") (pin "SCL") (pinfunction "SCL_SCL") (pintype "unspecified"))
    )
    (net (code "107") (name "unconnected-(U9-PadSDA)") (class "Default")
      (node (ref "U9") (pin "SDA") (pinfunction "SDA_SDA") (pintype "unspecified"))
    )
    (net (code "108") (name "unconnected-(U10-FUTURE-PadRESERVED)") (class "Default")
      (node (ref "U10") (pin "RESERVED") (pinfunction "FUTURE_RESERVED") (pintype "unspecified"))
    )
    (net (code "109") (name "unconnected-(U10-GND2-PadGND$2)") (class "Default")
      (node (ref "U10") (pin "GND$2") (pinfunction "GND2_GND$2") (pintype "passive"))
    )
    (net (code "110") (name "unconnected-(U10-Pad3V)") (class "Default")
      (node (ref "U10") (pin "3V") (pinfunction "3V_3V") (pintype "passive"))
    )
    (net (code "111") (name "unconnected-(U10-PadA0)") (class "Default")
      (node (ref "U10") (pin "A0") (pinfunction "A0_A0") (pintype "unspecified"))
    )
    (net (code "112") (name "unconnected-(U10-PadA1)") (class "Default")
      (node (ref "U10") (pin "A1") (pinfunction "A1_A1") (pintype "unspecified"))
    )
    (net (code "113") (name "unconnected-(U10-PadA2)") (class "Default")
      (node (ref "U10") (pin "A2") (pinfunction "A2_A2") (pintype "unspecified"))
    )
    (net (code "114") (name "unconnected-(U10-PadA3)") (class "Default")
      (node (ref "U10") (pin "A3") (pinfunction "A3_A3") (pintype "unspecified"))
    )
    (net (code "115") (name "unconnected-(U10-PadA4)") (class "Default")
      (node (ref "U10") (pin "A4") (pinfunction "A4_A4") (pintype "unspecified"))
    )
    (net (code "116") (name "unconnected-(U10-PadA5)") (class "Default")
      (node (ref "U10") (pin "A5") (pinfunction "A5_A5") (pintype "unspecified"))
    )
    (net (code "117") (name "unconnected-(U10-PadAREF)") (class "Default")
      (node (ref "U10") (pin "AREF") (pinfunction "AREF_AREF") (pintype "unspecified"))
    )
    (net (code "118") (name "unconnected-(U10-PadD0)") (class "Default")
      (node (ref "U10") (pin "D0") (pinfunction "D0_D0") (pintype "unspecified"))
    )
    (net (code "119") (name "unconnected-(U10-PadD1)") (class "Default")
      (node (ref "U10") (pin "D1") (pinfunction "D1_D1") (pintype "unspecified"))
    )
    (net (code "120") (name "unconnected-(U10-PadD2)") (class "Default")
      (node (ref "U10") (pin "D2") (pinfunction "D2_D2") (pintype "unspecified"))
    )
    (net (code "121") (name "unconnected-(U10-PadD3)") (class "Default")
      (node (ref "U10") (pin "D3") (pinfunction "D3_D3") (pintype "unspecified"))
    )
    (net (code "122") (name "unconnected-(U10-PadD4)") (class "Default")
      (node (ref "U10") (pin "D4") (pinfunction "D4_D4") (pintype "unspecified"))
    )
    (net (code "123") (name "unconnected-(U10-PadD5)") (class "Default")
      (node (ref "U10") (pin "D5") (pinfunction "D5_D5") (pintype "unspecified"))
    )
    (net (code "124") (name "unconnected-(U10-PadD10)") (class "Default")
      (node (ref "U10") (pin "D10") (pinfunction "D10_D10") (pintype "unspecified"))
    )
    (net (code "125") (name "unconnected-(U10-PadD11)") (class "Default")
      (node (ref "U10") (pin "D11") (pinfunction "D11_D11") (pintype "unspecified"))
    )
    (net (code "126") (name "unconnected-(U10-PadD12)") (class "Default")
      (node (ref "U10") (pin "D12") (pinfunction "D12_D12") (pintype "unspecified"))
    )
    (net (code "127") (name "unconnected-(U10-PadD13)") (class "Default")
      (node (ref "U10") (pin "D13") (pinfunction "D13_D13") (pintype "unspecified"))
    )
    (net (code "128") (name "unconnected-(U10-PadGND)") (class "Default")
      (node (ref "U10") (pin "GND") (pinfunction "GND_GND") (pintype "passive"))
    )
    (net (code "129") (name "unconnected-(U10-PadIOREF)") (class "Default")
      (node (ref "U10") (pin "IOREF") (pinfunction "IOREF_IOREF") (pintype "unspecified"))
    )
    (net (code "130") (name "unconnected-(U10-PadRESET)") (class "Default")
      (node (ref "U10") (pin "RESET") (pinfunction "RESET_RESET") (pintype "unspecified"))
    )
    (net (code "131") (name "unconnected-(U10-PadSCL)") (class "Default")
      (node (ref "U10") (pin "SCL") (pinfunction "SCL_SCL") (pintype "unspecified"))
    )
    (net (code "132") (name "unconnected-(U10-PadSDA)") (class "Default")
      (node (ref "U10") (pin "SDA") (pinfunction "SDA_SDA") (pintype "unspecified"))
    )
    (net (code "133") (name "unconnected-(U11-FUTURE-PadRESERVED)") (class "Default")
      (node (ref "U11") (pin "RESERVED") (pinfunction "FUTURE_RESERVED") (pintype "unspecified"))
    )
    (net (code "134") (name "unconnected-(U11-GND2-PadGND$2)") (class "Default")
      (node (ref "U11") (pin "GND$2") (pinfunction "GND2_GND$2") (pintype "passive"))
    )
    (net (code "135") (name "unconnected-(U11-Pad3V)") (class "Default")
      (node (ref "U11") (pin "3V") (pinfunction "3V_3V") (pintype "passive"))
    )
    (net (code "136") (name "unconnected-(U11-PadAREF)") (class "Default")
      (node (ref "U11") (pin "AREF") (pinfunction "AREF_AREF") (pintype "unspecified"))
    )
    (net (code "137") (name "unconnected-(U11-PadD4)") (class "Default")
      (node (ref "U11") (pin "D4") (pinfunction "D4_D4") (pintype "unspecified"))
    )
    (net (code "138") (name "unconnected-(U11-PadD5)") (class "Default")
      (node (ref "U11") (pin "D5") (pinfunction "D5_D5") (pintype "unspecified"))
    )
    (net (code "139") (name "unconnected-(U11-PadD10)") (class "Default")
      (node (ref "U11") (pin "D10") (pinfunction "D10_D10") (pintype "unspecified"))
    )
    (net (code "140") (name "unconnected-(U11-PadD11)") (class "Default")
      (node (ref "U11") (pin "D11") (pinfunction "D11_D11") (pintype "unspecified"))
    )
    (net (code "141") (name "unconnected-(U11-PadD12)") (class "Default")
      (node (ref "U11") (pin "D12") (pinfunction "D12_D12") (pintype "unspecified"))
    )
    (net (code "142") (name "unconnected-(U11-PadD13)") (class "Default")
      (node (ref "U11") (pin "D13") (pinfunction "D13_D13") (pintype "unspecified"))
    )
    (net (code "143") (name "unconnected-(U11-PadGND)") (class "Default")
      (node (ref "U11") (pin "GND") (pinfunction "GND_GND") (pintype "passive"))
    )
    (net (code "144") (name "unconnected-(U11-PadIOREF)") (class "Default")
      (node (ref "U11") (pin "IOREF") (pinfunction "IOREF_IOREF") (pintype "unspecified"))
    )
    (net (code "145") (name "unconnected-(U11-PadRESET)") (class "Default")
      (node (ref "U11") (pin "RESET") (pinfunction "RESET_RESET") (pintype "unspecified"))
    )
    (net (code "146") (name "unconnected-(U11-PadSCL)") (class "Default")
      (node (ref "U11") (pin "SCL") (pinfunction "SCL_SCL") (pintype "unspecified"))
    )
    (net (code "147") (name "unconnected-(U11-PadSDA)") (class "Default")
      (node (ref "U11") (pin "SDA") (pinfunction "SDA_SDA") (pintype "unspecified"))
    )
    (net (code "148") (name "unconnected-(U12-\"1\"-Pad2)") (class "Default")
      (node (ref "U12") (pin "2") (pinfunction "\"1\"_2") (pintype "unspecified"))
    )
    (net (code "149") (name "unconnected-(U12-\"8\"-Pad9)") (class "Default")
      (node (ref "U12") (pin "9") (pinfunction "\"8\"_9") (pintype "unspecified"))
    )
    (net (code "150") (name "unconnected-(U12-3.3V_BYP-Pad10)") (class "Default")
      (node (ref "U12") (pin "10") (pinfunction "3.3V_BYP_10") (pintype "unspecified"))
    )
    (net (code "151") (name "unconnected-(U12-3.3V_BYP-Pad11)") (class "Default")
      (node (ref "U12") (pin "11") (pinfunction "3.3V_BYP_11") (pintype "unspecified"))
    )
  )
)
